# DXP_sc.net
KiCad netlist of a schematic drawn in Altium Designer
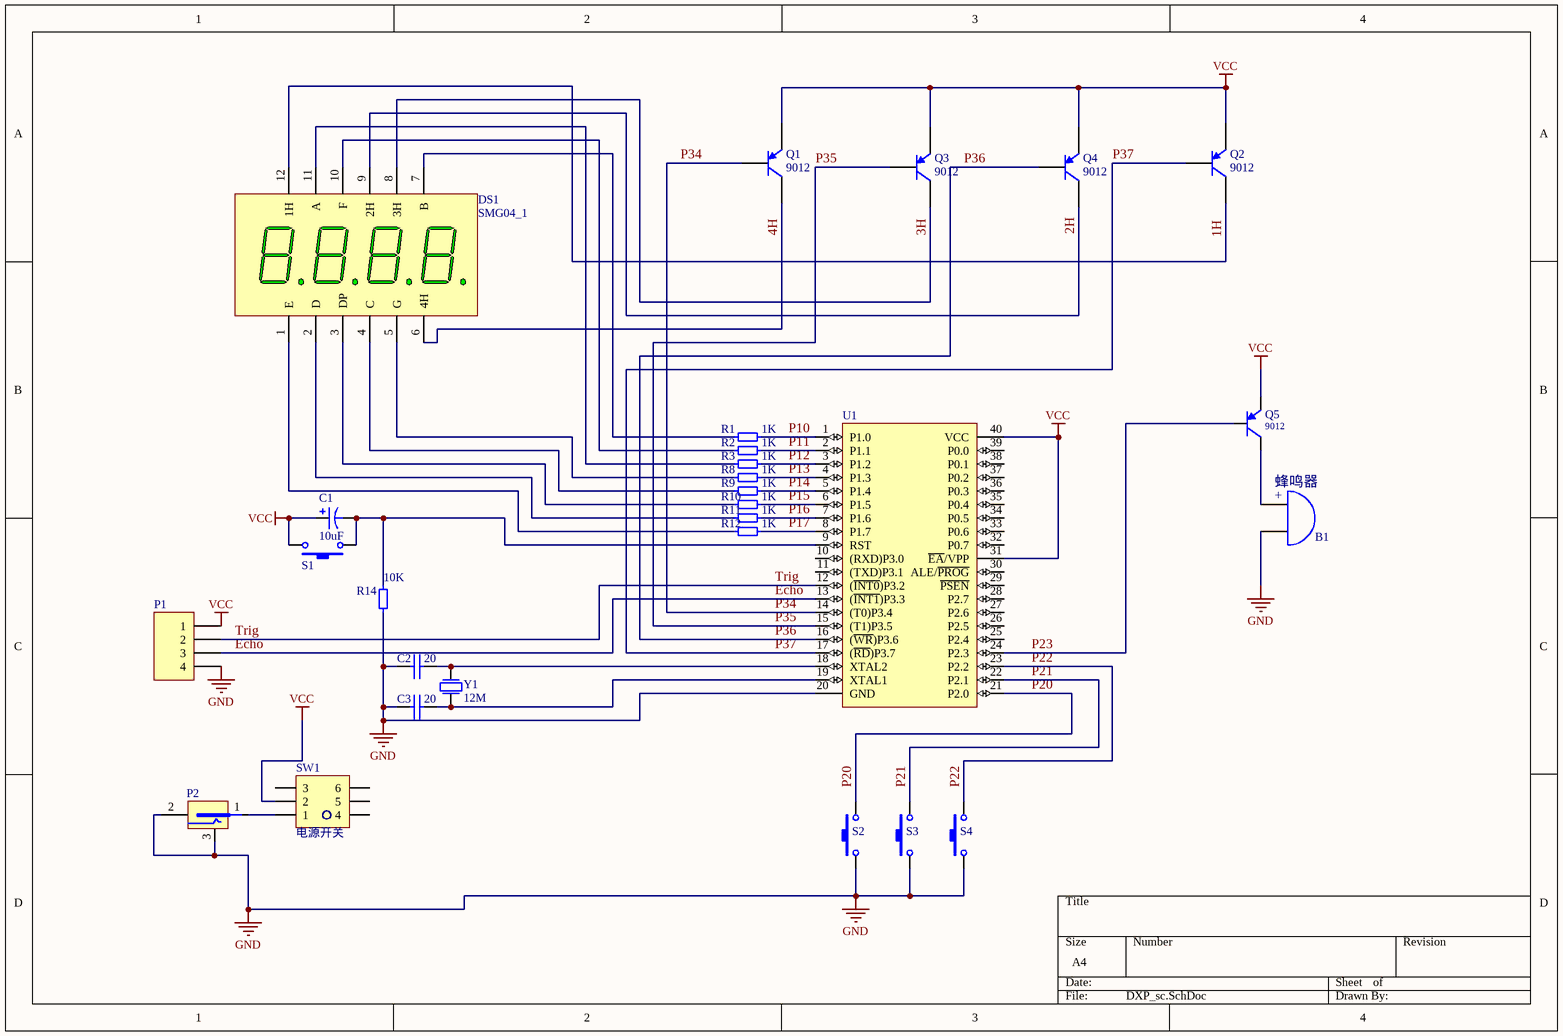
[diagram p0: DXP_sc.SchDoc]

(export (version "E")
  (design (tool "Eeschema 10.0.6"))
  (components
    (comp (ref "B1")
      (value "蜂鸣器")
      (footprint "Bett")
      (description "Bell")
      (libsource (lib "实验板原理图") (part "BELL"))
    )
    (comp (ref "C1")
      (value "10uF")
      (footprint "C_10")
      (description "Polarized Capacitor (Radial)")
      (fields (field (name "PUBLISHER") "Altium Limited"))
      (libsource (lib "简易动环监控系统") (part "Cap Pol1"))
    )
    (comp (ref "C2")
      (value "20")
      (footprint "CAP CP")
      (description "电容")
      (libsource (lib "C8051F020最小2") (part "CAP"))
    )
    (comp (ref "C3")
      (value "20")
      (footprint "CAP CP")
      (description "电容")
      (libsource (lib "C8051F020最小2") (part "CAP"))
    )
    (comp (ref "DS1") (value "SMG04_1") (footprint "SMG04") (libsource (lib "我自己的") (part "SMG04_1")))
    (comp (ref "P1")
      (value "Header 4")
      (footprint "HDR1X4")
      (description "Header, 4-Pin")
      (fields (field (name "PUBLISHER") "Altium Limited"))
      (libsource (lib "Miscellaneous Connectors") (part "Header 4"))
    )
    (comp (ref "P2") (value "电源输入") (footprint "DC2.1") (libsource (lib "我自己的") (part "POWER")))
    (comp (ref "Q1")
      (value "9012")
      (footprint "s三极管直插")
      (description "PNP General Purpose Amplifier")
      (fields (field (name "PUBLISHER") "Altium Limited"))
      (libsource (lib "Miscellaneous Devices") (part "2N3906"))
    )
    (comp (ref "Q2")
      (value "9012")
      (footprint "s三极管直插")
      (description "PNP General Purpose Amplifier")
      (fields (field (name "PUBLISHER") "Altium Limited"))
      (libsource (lib "Miscellaneous Devices") (part "2N3906"))
    )
    (comp (ref "Q3")
      (value "9012")
      (footprint "s三极管直插")
      (description "PNP General Purpose Amplifier")
      (fields (field (name "PUBLISHER") "Altium Limited"))
      (libsource (lib "Miscellaneous Devices") (part "2N3906"))
    )
    (comp (ref "Q4")
      (value "9012")
      (footprint "s三极管直插")
      (description "PNP General Purpose Amplifier")
      (fields (field (name "PUBLISHER") "Altium Limited"))
      (libsource (lib "Miscellaneous Devices") (part "2N3906"))
    )
    (comp (ref "Q5")
      (value "9012")
      (footprint "s三极管直插")
      (description "PNP General Purpose Amplifier")
      (fields (field (name "PUBLISHER") "Altium Limited"))
      (libsource (lib "实验板原理图") (part "2N3906"))
    )
    (comp (ref "R1") (value "1K") (footprint "AXIAL0.3") (libsource (lib "C8051F020最小2") (part "RES2")))
    (comp (ref "R2") (value "1K") (footprint "AXIAL0.3") (libsource (lib "C8051F020最小2") (part "RES2")))
    (comp (ref "R3") (value "1K") (footprint "AXIAL0.3") (libsource (lib "C8051F020最小2") (part "RES2")))
    (comp (ref "R8") (value "1K") (footprint "AXIAL0.3") (libsource (lib "C8051F020最小2") (part "RES2")))
    (comp (ref "R9") (value "1K") (footprint "AXIAL0.3") (libsource (lib "C8051F020最小2") (part "RES2")))
    (comp (ref "R10") (value "1K") (footprint "AXIAL0.3") (libsource (lib "C8051F020最小2") (part "RES2")))
    (comp (ref "R11") (value "1K") (footprint "AXIAL0.3") (libsource (lib "C8051F020最小2") (part "RES2")))
    (comp (ref "R12") (value "1K") (footprint "AXIAL0.3") (libsource (lib "C8051F020最小2") (part "RES2")))
    (comp (ref "R14") (value "10K") (footprint "AXIAL0.3") (libsource (lib "C8051F020最小2") (part "RES2")))
    (comp (ref "S1")
      (value "SW-PB")
      (footprint "key")
      (description "Switch")
      (fields (field (name "PUBLISHER") "Altium Limited"))
      (libsource (lib "实验板原理图") (part "SW-PB"))
    )
    (comp (ref "S2")
      (value "SW-PB")
      (footprint "key")
      (description "Switch")
      (fields (field (name "PUBLISHER") "Altium Limited"))
      (libsource (lib "实验板原理图") (part "SW-PB"))
    )
    (comp (ref "S3")
      (value "SW-PB")
      (footprint "key")
      (description "Switch")
      (fields (field (name "PUBLISHER") "Altium Limited"))
      (libsource (lib "实验板原理图") (part "SW-PB"))
    )
    (comp (ref "S4")
      (value "SW-PB")
      (footprint "key")
      (description "Switch")
      (fields (field (name "PUBLISHER") "Altium Limited"))
      (libsource (lib "实验板原理图") (part "SW-PB"))
    )
    (comp (ref "SW1") (value "电源开关") (footprint "sw_自锁 1") (libsource (lib "我自己的") (part "SW1")))
    (comp (ref "U1") (value "STC89C52") (footprint "DIP40 - 做板") (libsource (lib "实验板原理图") (part "U1")))
    (comp (ref "Y1")
      (value "12M")
      (footprint "XTAL")
      (description "Crystal Oscillator")
      (libsource (lib "C8051F020最小2") (part "16M"))
    )
  )
  (nets
    (net (code "1") (name "/1H") (class "Default")
      (node (ref "DS1") (pin "12") (pinfunction "1H_12") (pintype "passive"))
      (node (ref "Q2") (pin "3") (pinfunction "C_3") (pintype "passive"))
    )
    (net (code "2") (name "/2H") (class "Default")
      (node (ref "DS1") (pin "9") (pinfunction "2H_9") (pintype "passive"))
      (node (ref "Q4") (pin "3") (pinfunction "C_3") (pintype "passive"))
    )
    (net (code "3") (name "/3H") (class "Default")
      (node (ref "DS1") (pin "8") (pinfunction "3H_8") (pintype "passive"))
      (node (ref "Q3") (pin "3") (pinfunction "C_3") (pintype "passive"))
    )
    (net (code "4") (name "/4H") (class "Default")
      (node (ref "DS1") (pin "6") (pinfunction "4H_6") (pintype "passive"))
      (node (ref "Q1") (pin "3") (pinfunction "C_3") (pintype "passive"))
    )
    (net (code "5") (name "/Echo") (class "Default")
      (node (ref "P1") (pin "3") (pinfunction "3_3") (pintype "passive"))
      (node (ref "U1") (pin "13") (pinfunction "(~{INT1})P3.3_13") (pintype "bidirectional"))
    )
    (net (code "6") (name "/P10") (class "Default")
      (node (ref "R1") (pin "1") (pinfunction "1_1") (pintype "passive"))
      (node (ref "U1") (pin "1") (pinfunction "P1.0_1") (pintype "bidirectional"))
    )
    (net (code "7") (name "/P11") (class "Default")
      (node (ref "R2") (pin "1") (pinfunction "1_1") (pintype "passive"))
      (node (ref "U1") (pin "2") (pinfunction "P1.1_2") (pintype "bidirectional"))
    )
    (net (code "8") (name "/P12") (class "Default")
      (node (ref "R3") (pin "1") (pinfunction "1_1") (pintype "passive"))
      (node (ref "U1") (pin "3") (pinfunction "P1.2_3") (pintype "bidirectional"))
    )
    (net (code "9") (name "/P13") (class "Default")
      (node (ref "R8") (pin "1") (pinfunction "1_1") (pintype "passive"))
      (node (ref "U1") (pin "4") (pinfunction "P1.3_4") (pintype "bidirectional"))
    )
    (net (code "10") (name "/P14") (class "Default")
      (node (ref "R9") (pin "1") (pinfunction "1_1") (pintype "passive"))
      (node (ref "U1") (pin "5") (pinfunction "P1.4_5") (pintype "bidirectional"))
    )
    (net (code "11") (name "/P15") (class "Default")
      (node (ref "R10") (pin "1") (pinfunction "1_1") (pintype "passive"))
      (node (ref "U1") (pin "6") (pinfunction "P1.5_6") (pintype "bidirectional"))
    )
    (net (code "12") (name "/P16") (class "Default")
      (node (ref "R11") (pin "1") (pinfunction "1_1") (pintype "passive"))
      (node (ref "U1") (pin "7") (pinfunction "P1.6_7") (pintype "bidirectional"))
    )
    (net (code "13") (name "/P17") (class "Default")
      (node (ref "R12") (pin "1") (pinfunction "1_1") (pintype "passive"))
      (node (ref "U1") (pin "8") (pinfunction "P1.7_8") (pintype "bidirectional"))
    )
    (net (code "14") (name "/P20") (class "Default")
      (node (ref "S2") (pin "2") (pinfunction "2_2") (pintype "passive"))
      (node (ref "U1") (pin "21") (pinfunction "P2.0_21") (pintype "bidirectional"))
    )
    (net (code "15") (name "/P21") (class "Default")
      (node (ref "S3") (pin "2") (pinfunction "2_2") (pintype "passive"))
      (node (ref "U1") (pin "22") (pinfunction "P2.1_22") (pintype "bidirectional"))
    )
    (net (code "16") (name "/P22") (class "Default")
      (node (ref "S4") (pin "2") (pinfunction "2_2") (pintype "passive"))
      (node (ref "U1") (pin "23") (pinfunction "P2.2_23") (pintype "bidirectional"))
    )
    (net (code "17") (name "/P23") (class "Default")
      (node (ref "Q5") (pin "2") (pinfunction "B_2") (pintype "passive"))
      (node (ref "U1") (pin "24") (pinfunction "P2.3_24") (pintype "bidirectional"))
    )
    (net (code "18") (name "/P34") (class "Default")
      (node (ref "Q1") (pin "2") (pinfunction "B_2") (pintype "passive"))
      (node (ref "U1") (pin "14") (pinfunction "(T0)P3.4_14") (pintype "bidirectional"))
    )
    (net (code "19") (name "/P35") (class "Default")
      (node (ref "Q3") (pin "2") (pinfunction "B_2") (pintype "passive"))
      (node (ref "U1") (pin "15") (pinfunction "(T1)P3.5_15") (pintype "bidirectional"))
    )
    (net (code "20") (name "/P36") (class "Default")
      (node (ref "Q4") (pin "2") (pinfunction "B_2") (pintype "passive"))
      (node (ref "U1") (pin "16") (pinfunction "(~{WR})P3.6_16") (pintype "bidirectional"))
    )
    (net (code "21") (name "/P37") (class "Default")
      (node (ref "Q2") (pin "2") (pinfunction "B_2") (pintype "passive"))
      (node (ref "U1") (pin "17") (pinfunction "(~{RD})P3.7_17") (pintype "bidirectional"))
    )
    (net (code "22") (name "/Trig") (class "Default")
      (node (ref "P1") (pin "2") (pinfunction "2_2") (pintype "passive"))
      (node (ref "U1") (pin "12") (pinfunction "(~{INT0})P3.2_12") (pintype "bidirectional"))
    )
    (net (code "23") (name "GND") (class "Default")
      (node (ref "B1") (pin "2") (pinfunction "B_2") (pintype "passive"))
      (node (ref "C2") (pin "1") (pinfunction "1_1") (pintype "passive"))
      (node (ref "C3") (pin "1") (pinfunction "1_1") (pintype "passive"))
      (node (ref "P1") (pin "4") (pinfunction "4_4") (pintype "passive"))
      (node (ref "P2") (pin "2") (pintype "passive"))
      (node (ref "P2") (pin "3") (pintype "passive"))
      (node (ref "R14") (pin "1") (pinfunction "1_1") (pintype "passive"))
      (node (ref "S2") (pin "1") (pinfunction "1_1") (pintype "passive"))
      (node (ref "S3") (pin "1") (pinfunction "1_1") (pintype "passive"))
      (node (ref "S4") (pin "1") (pinfunction "1_1") (pintype "passive"))
      (node (ref "U1") (pin "20") (pinfunction "GND_20") (pintype "power_in"))
    )
    (net (code "24") (name "Net-(B1-A)") (class "Default")
      (node (ref "B1") (pin "1") (pinfunction "A_1") (pintype "passive"))
      (node (ref "Q5") (pin "3") (pinfunction "C_3") (pintype "passive"))
    )
    (net (code "25") (name "Net-(DS1-A)") (class "Default")
      (node (ref "DS1") (pin "11") (pinfunction "A_11") (pintype "passive"))
      (node (ref "R3") (pin "2") (pinfunction "2_2") (pintype "passive"))
    )
    (net (code "26") (name "Net-(DS1-B)") (class "Default")
      (node (ref "DS1") (pin "7") (pinfunction "B_7") (pintype "passive"))
      (node (ref "R1") (pin "2") (pinfunction "2_2") (pintype "passive"))
    )
    (net (code "27") (name "Net-(DS1-C)") (class "Default")
      (node (ref "DS1") (pin "4") (pinfunction "C_4") (pintype "passive"))
      (node (ref "R9") (pin "2") (pinfunction "2_2") (pintype "passive"))
    )
    (net (code "28") (name "Net-(DS1-D)") (class "Default")
      (node (ref "DS1") (pin "2") (pinfunction "D_2") (pintype "passive"))
      (node (ref "R11") (pin "2") (pinfunction "2_2") (pintype "passive"))
    )
    (net (code "29") (name "Net-(DS1-DP)") (class "Default")
      (node (ref "DS1") (pin "3") (pinfunction "DP_3") (pintype "passive"))
      (node (ref "R10") (pin "2") (pinfunction "2_2") (pintype "passive"))
    )
    (net (code "30") (name "Net-(DS1-E)") (class "Default")
      (node (ref "DS1") (pin "1") (pinfunction "E_1") (pintype "passive"))
      (node (ref "R12") (pin "2") (pinfunction "2_2") (pintype "passive"))
    )
    (net (code "31") (name "Net-(DS1-F)") (class "Default")
      (node (ref "DS1") (pin "10") (pinfunction "F_10") (pintype "passive"))
      (node (ref "R2") (pin "2") (pinfunction "2_2") (pintype "passive"))
    )
    (net (code "32") (name "Net-(DS1-G)") (class "Default")
      (node (ref "DS1") (pin "5") (pinfunction "G_5") (pintype "passive"))
      (node (ref "R8") (pin "2") (pinfunction "2_2") (pintype "passive"))
    )
    (net (code "33") (name "Net-(P2-Pad1)") (class "Default")
      (node (ref "P2") (pin "1") (pintype "passive"))
      (node (ref "SW1") (pin "1") (pinfunction "1_1") (pintype "passive"))
    )
    (net (code "34") (name "Net-(U1-RST)") (class "Default")
      (node (ref "C1") (pin "2") (pinfunction "2_2") (pintype "passive"))
      (node (ref "R14") (pin "2") (pinfunction "2_2") (pintype "passive"))
      (node (ref "S1") (pin "1") (pinfunction "1_1") (pintype "passive"))
      (node (ref "U1") (pin "9") (pinfunction "RST_9") (pintype "bidirectional"))
    )
    (net (code "35") (name "Net-(U1-XTAL1)") (class "Default")
      (node (ref "C3") (pin "2") (pinfunction "2_2") (pintype "passive"))
      (node (ref "U1") (pin "19") (pinfunction "XTAL1_19") (pintype "bidirectional"))
      (node (ref "Y1") (pin "2") (pinfunction "P2_2") (pintype "passive"))
    )
    (net (code "36") (name "Net-(U1-XTAL2)") (class "Default")
      (node (ref "C2") (pin "2") (pinfunction "2_2") (pintype "passive"))
      (node (ref "U1") (pin "18") (pinfunction "XTAL2_18") (pintype "bidirectional"))
      (node (ref "Y1") (pin "1") (pinfunction "P1_1") (pintype "passive"))
    )
    (net (code "37") (name "VCC") (class "Default")
      (node (ref "C1") (pin "1") (pinfunction "1_1") (pintype "passive"))
      (node (ref "P1") (pin "1") (pinfunction "1_1") (pintype "passive"))
      (node (ref "Q1") (pin "1") (pinfunction "E_1") (pintype "passive"))
      (node (ref "Q2") (pin "1") (pinfunction "E_1") (pintype "passive"))
      (node (ref "Q3") (pin "1") (pinfunction "E_1") (pintype "passive"))
      (node (ref "Q4") (pin "1") (pinfunction "E_1") (pintype "passive"))
      (node (ref "Q5") (pin "1") (pinfunction "E_1") (pintype "passive"))
      (node (ref "S1") (pin "2") (pinfunction "2_2") (pintype "passive"))
      (node (ref "SW1") (pin "2") (pinfunction "2_2") (pintype "passive"))
      (node (ref "U1") (pin "31") (pinfunction "~{EA}/VPP_31") (pintype "power_in"))
      (node (ref "U1") (pin "40") (pinfunction "VCC_40") (pintype "power_in"))
    )
    (net (code "38") (name "unconnected-(SW1-Pad3)") (class "Default")
      (node (ref "SW1") (pin "3") (pinfunction "3_3") (pintype "passive"))
    )
    (net (code "39") (name "unconnected-(SW1-Pad4)") (class "Default")
      (node (ref "SW1") (pin "4") (pinfunction "4_4") (pintype "passive"))
    )
    (net (code "40") (name "unconnected-(SW1-Pad5)") (class "Default")
      (node (ref "SW1") (pin "5") (pinfunction "5_5") (pintype "passive"))
    )
    (net (code "41") (name "unconnected-(SW1-Pad6)") (class "Default")
      (node (ref "SW1") (pin "6") (pinfunction "6_6") (pintype "passive"))
    )
    (net (code "42") (name "unconnected-(U1-(RXD)P3.0-Pad10)") (class "Default")
      (node (ref "U1") (pin "10") (pinfunction "(RXD)P3.0_10") (pintype "bidirectional"))
    )
    (net (code "43") (name "unconnected-(U1-(TXD)P3.1-Pad11)") (class "Default")
      (node (ref "U1") (pin "11") (pinfunction "(TXD)P3.1_11") (pintype "bidirectional"))
    )
    (net (code "44") (name "unconnected-(U1-ALE{slash}~{PROG}-Pad30)") (class "Default")
      (node (ref "U1") (pin "30") (pinfunction "ALE/~{PROG}_30") (pintype "bidirectional"))
    )
    (net (code "45") (name "unconnected-(U1-P0.0-Pad39)") (class "Default")
      (node (ref "U1") (pin "39") (pinfunction "P0.0_39") (pintype "bidirectional"))
    )
    (net (code "46") (name "unconnected-(U1-P0.1-Pad38)") (class "Default")
      (node (ref "U1") (pin "38") (pinfunction "P0.1_38") (pintype "bidirectional"))
    )
    (net (code "47") (name "unconnected-(U1-P0.2-Pad37)") (class "Default")
      (node (ref "U1") (pin "37") (pinfunction "P0.2_37") (pintype "bidirectional"))
    )
    (net (code "48") (name "unconnected-(U1-P0.3-Pad36)") (class "Default")
      (node (ref "U1") (pin "36") (pinfunction "P0.3_36") (pintype "bidirectional"))
    )
    (net (code "49") (name "unconnected-(U1-P0.4-Pad35)") (class "Default")
      (node (ref "U1") (pin "35") (pinfunction "P0.4_35") (pintype "bidirectional"))
    )
    (net (code "50") (name "unconnected-(U1-P0.5-Pad34)") (class "Default")
      (node (ref "U1") (pin "34") (pinfunction "P0.5_34") (pintype "bidirectional"))
    )
    (net (code "51") (name "unconnected-(U1-P0.6-Pad33)") (class "Default")
      (node (ref "U1") (pin "33") (pinfunction "P0.6_33") (pintype "bidirectional"))
    )
    (net (code "52") (name "unconnected-(U1-P0.7-Pad32)") (class "Default")
      (node (ref "U1") (pin "32") (pinfunction "P0.7_32") (pintype "bidirectional"))
    )
    (net (code "53") (name "unconnected-(U1-P2.4-Pad25)") (class "Default")
      (node (ref "U1") (pin "25") (pinfunction "P2.4_25") (pintype "bidirectional"))
    )
    (net (code "54") (name "unconnected-(U1-P2.5-Pad26)") (class "Default")
      (node (ref "U1") (pin "26") (pinfunction "P2.5_26") (pintype "bidirectional"))
    )
    (net (code "55") (name "unconnected-(U1-P2.6-Pad27)") (class "Default")
      (node (ref "U1") (pin "27") (pinfunction "P2.6_27") (pintype "bidirectional"))
    )
    (net (code "56") (name "unconnected-(U1-P2.7-Pad28)") (class "Default")
      (node (ref "U1") (pin "28") (pinfunction "P2.7_28") (pintype "bidirectional"))
    )
    (net (code "57") (name "unconnected-(U1-~{PSEN}-Pad29)") (class "Default")
      (node (ref "U1") (pin "29") (pinfunction "~{PSEN}_29") (pintype "bidirectional"))
    )
  )
)
